# WeeMouse.net
KiCad netlist of a schematic drawn in Altium Designer
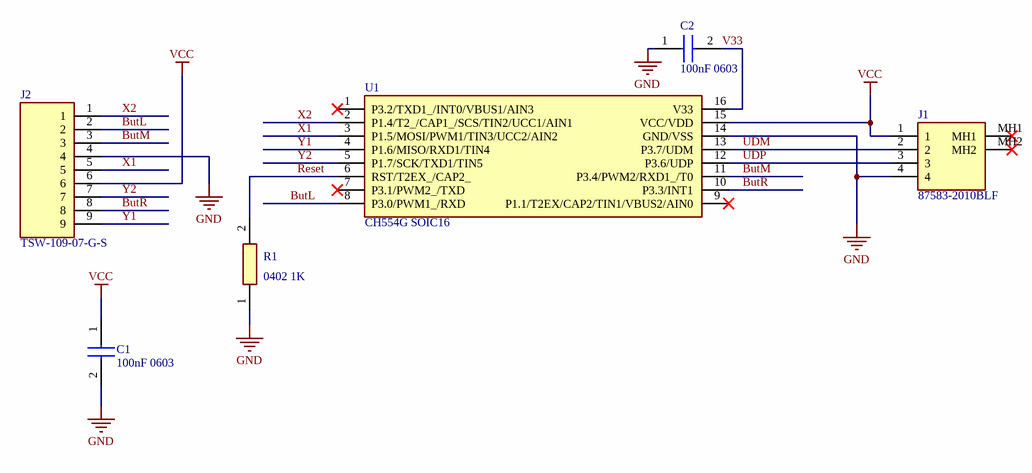
[diagram p0: WeeMouse.SchDoc]

(export (version "E")
  (design (tool "Eeschema 10.0.6"))
  (components
    (comp (ref "C1")
      (value "100nF 0603")
      (footprint "SamacSys:CAPC1608X90N")
      (description "Capacitor")
      (fields
        (field (name "MANUFACTURER_PART_NUMBER") "06033C104KAT4A")
        (field (name "MOUSER PART NUMBER") "581-06033C104KAT4A")
      )
      (libsource (lib "SamacSys") (part "06033C104KAT4A"))
    )
    (comp (ref "C2")
      (value "100nF 0603")
      (footprint "SamacSys:CAPC1608X90N")
      (description "Capacitor")
      (fields
        (field (name "MANUFACTURER_PART_NUMBER") "06033C104KAT4A")
        (field (name "MOUSER PART NUMBER") "581-06033C104KAT4A")
      )
      (libsource (lib "SamacSys") (part "06033C104KAT4A"))
    )
    (comp (ref "J1")
      (value "87583-2010BLF")
      (footprint "SamacSys:875832010BLF")
      (description "Connector")
      (libsource (lib "*") (part "87583-2010BLF"))
    )
    (comp (ref "J2")
      (value "TSW-109-07-G-S")
      (footprint "SamacSys:TSW-109-XX-YY-S")
      (description "Connector")
      (fields (field (name "MOUSER PART NUMBER") "200-TSW10907GS"))
      (libsource (lib "*") (part "TSW-109-07-G-S"))
    )
    (comp (ref "R1")
      (value "0402 1K")
      (footprint "SamacSys:RESC1005X40N")
      (description "Resistor")
      (fields
        (field (name "MANUFACTURER_PART_NUMBER") "CRCW04021K00JNED")
        (field (name "MOUSER PART NUMBER") "71-CRCW0402J-1.0K-E3")
      )
      (libsource (lib "SamacSys") (part "CRCW04021K00JNED"))
    )
    (comp (ref "U1")
      (value "CH554G SOIC16")
      (footprint "SamacSys:SOIC127P600X175-16N")
      (description "8051 MCU with USB host")
      (fields (field (name "MANUFACTURER_PART_NUMBER") "MM74HC4049M"))
      (libsource (lib "SamacSys") (part "CH544G"))
    )
  )
  (nets
    (net (code "1") (name "/ButL") (class "Default")
      (node (ref "J2") (pin "2") (pinfunction "2_2") (pintype "passive"))
      (node (ref "U1") (pin "8") (pinfunction "P3.0/PWM1_/RXD_8") (pintype "passive"))
    )
    (net (code "2") (name "/ButM") (class "Default")
      (node (ref "J2") (pin "3") (pinfunction "3_3") (pintype "passive"))
      (node (ref "U1") (pin "11") (pinfunction "P3.4/PWM2/RXD1_/T0_11") (pintype "passive"))
    )
    (net (code "3") (name "/ButR") (class "Default")
      (node (ref "J2") (pin "8") (pinfunction "8_8") (pintype "passive"))
      (node (ref "U1") (pin "10") (pinfunction "P3.3/INT1_10") (pintype "passive"))
    )
    (net (code "4") (name "/Reset") (class "Default")
      (node (ref "R1") (pin "2") (pinfunction "2_2") (pintype "passive"))
      (node (ref "U1") (pin "6") (pinfunction "RST/T2EX_/CAP2__6") (pintype "passive"))
    )
    (net (code "5") (name "/UDM") (class "Default")
      (node (ref "J1") (pin "2") (pinfunction "2_2") (pintype "passive"))
      (node (ref "U1") (pin "13") (pinfunction "P3.7/UDM_13") (pintype "passive"))
    )
    (net (code "6") (name "/UDP") (class "Default")
      (node (ref "J1") (pin "3") (pinfunction "3_3") (pintype "passive"))
      (node (ref "U1") (pin "12") (pinfunction "P3.6/UDP_12") (pintype "passive"))
    )
    (net (code "7") (name "/V33") (class "Default")
      (node (ref "C2") (pin "2") (pinfunction "2_2") (pintype "passive"))
      (node (ref "U1") (pin "16") (pinfunction "V33_16") (pintype "passive"))
    )
    (net (code "8") (name "/X1") (class "Default")
      (node (ref "J2") (pin "5") (pinfunction "5_5") (pintype "passive"))
      (node (ref "U1") (pin "3") (pinfunction "P1.5/MOSI/PWM1/TIN3/UCC2/AIN2_3") (pintype "passive"))
    )
    (net (code "9") (name "/X2") (class "Default")
      (node (ref "J2") (pin "1") (pinfunction "1_1") (pintype "passive"))
      (node (ref "U1") (pin "2") (pinfunction "P1.4/T2_/CAP1_/SCS/TIN2/UCC1/AIN1_2") (pintype "passive"))
    )
    (net (code "10") (name "/Y1") (class "Default")
      (node (ref "J2") (pin "9") (pinfunction "9_9") (pintype "passive"))
      (node (ref "U1") (pin "4") (pinfunction "P1.6/MISO/RXD1/TIN4_4") (pintype "passive"))
    )
    (net (code "11") (name "/Y2") (class "Default")
      (node (ref "J2") (pin "7") (pinfunction "7_7") (pintype "passive"))
      (node (ref "U1") (pin "5") (pinfunction "P1.7/SCK/TXD1/TIN5_5") (pintype "passive"))
    )
    (net (code "12") (name "GND") (class "Default")
      (node (ref "C1") (pin "2") (pinfunction "2_2") (pintype "passive"))
      (node (ref "C2") (pin "1") (pinfunction "1_1") (pintype "passive"))
      (node (ref "J1") (pin "4") (pinfunction "4_4") (pintype "passive"))
      (node (ref "J2") (pin "4") (pinfunction "4_4") (pintype "passive"))
      (node (ref "R1") (pin "1") (pinfunction "1_1") (pintype "passive"))
      (node (ref "U1") (pin "14") (pinfunction "GND/VSS_14") (pintype "passive"))
    )
    (net (code "13") (name "VCC") (class "Default")
      (node (ref "C1") (pin "1") (pinfunction "1_1") (pintype "passive"))
      (node (ref "J1") (pin "1") (pinfunction "1_1") (pintype "passive"))
      (node (ref "J2") (pin "6") (pinfunction "6_6") (pintype "passive"))
      (node (ref "U1") (pin "15") (pinfunction "VCC/VDD_15") (pintype "passive"))
    )
    (net (code "14") (name "unconnected-(J1-PadMH1)") (class "Default")
      (node (ref "J1") (pin "MH1") (pinfunction "MH1_MH1") (pintype "passive+no_connect"))
    )
    (net (code "15") (name "unconnected-(J1-PadMH2)") (class "Default")
      (node (ref "J1") (pin "MH2") (pinfunction "MH2_MH2") (pintype "passive+no_connect"))
    )
    (net (code "16") (name "unconnected-(U1-P1.1{slash}T2EX{slash}CAP2{slash}TIN1{slash}VBUS2{slash}AIN0-Pad9)") (class "Default")
      (node (ref "U1") (pin "9") (pinfunction "P1.1/T2EX/CAP2/TIN1/VBUS2/AIN0_9") (pintype "passive+no_connect"))
    )
    (net (code "17") (name "unconnected-(U1-P3.1{slash}PWM2_{slash}TXD-Pad7)") (class "Default")
      (node (ref "U1") (pin "7") (pinfunction "P3.1/PWM2_/TXD_7") (pintype "passive+no_connect"))
    )
    (net (code "18") (name "unconnected-(U1-P3.2{slash}TXD1_{slash}INT0{slash}VBUS1{slash}AIN3-Pad1)") (class "Default")
      (node (ref "U1") (pin "1") (pinfunction "P3.2/TXD1_/INT0/VBUS1/AIN3_1") (pintype "passive+no_connect"))
    )
  )
)
